# led.net
KiCad netlist of a schematic drawn in EAGLE
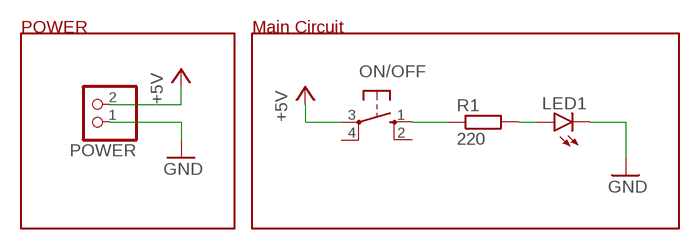
[diagram p0: schematic, sheet 1]

(export (version "E")
  (design (tool "Eeschema 10.0.6"))
  (components
    (comp (ref "LED1")
      (value "LED3MM")
      (footprint "eagle-import:LED3MM")
      (libsource (lib "eagle-import") (part "LED3MM"))
    )
    (comp (ref "ON/OFF")
      (value "10-XX")
      (footprint "eagle-import:B3F-10XX")
      (fields (field (name "MPN") "B3F-1000"))
      (libsource (lib "eagle-import") (part "10-XX"))
    )
    (comp (ref "POWER")
      (value "PINHD-1X2")
      (footprint "eagle-import:1X02")
      (libsource (lib "eagle-import") (part "PINHD-1X2"))
    )
    (comp (ref "R1")
      (value "220")
      (footprint "eagle-import:0204_7")
      (libsource (lib "eagle-import") (part "R-EU_0204/7"))
    )
  )
  (nets
    (net (code "1") (name "+5V") (class "Default")
      (node (ref "ON/OFF") (pin "3") (pinfunction "P_3") (pintype "passive"))
      (node (ref "POWER") (pin "2") (pinfunction "2_2") (pintype "passive"))
    )
    (net (code "2") (name "GND") (class "Default")
      (node (ref "LED1") (pin "K") (pinfunction "C_K") (pintype "passive"))
      (node (ref "POWER") (pin "1") (pinfunction "1_1") (pintype "passive"))
    )
    (net (code "3") (name "Net-(LED1-PadA)") (class "Default")
      (node (ref "LED1") (pin "A") (pinfunction "A_A") (pintype "passive"))
      (node (ref "R1") (pin "2") (pinfunction "2_2") (pintype "passive"))
    )
    (net (code "4") (name "Net-(ON/OFF-S)") (class "Default")
      (node (ref "ON/OFF") (pin "1") (pinfunction "S_1") (pintype "passive"))
      (node (ref "R1") (pin "1") (pinfunction "1_1") (pintype "passive"))
    )
    (net (code "5") (name "unconnected-(ON/OFF-P1-Pad4)") (class "Default")
      (node (ref "ON/OFF") (pin "4") (pinfunction "P1_4") (pintype "passive"))
    )
    (net (code "6") (name "unconnected-(ON/OFF-S1-Pad2)") (class "Default")
      (node (ref "ON/OFF") (pin "2") (pinfunction "S1_2") (pintype "passive"))
    )
  )
)
